# Clock_Updated_3_Nets.net
KiCad netlist of a schematic drawn in EAGLE
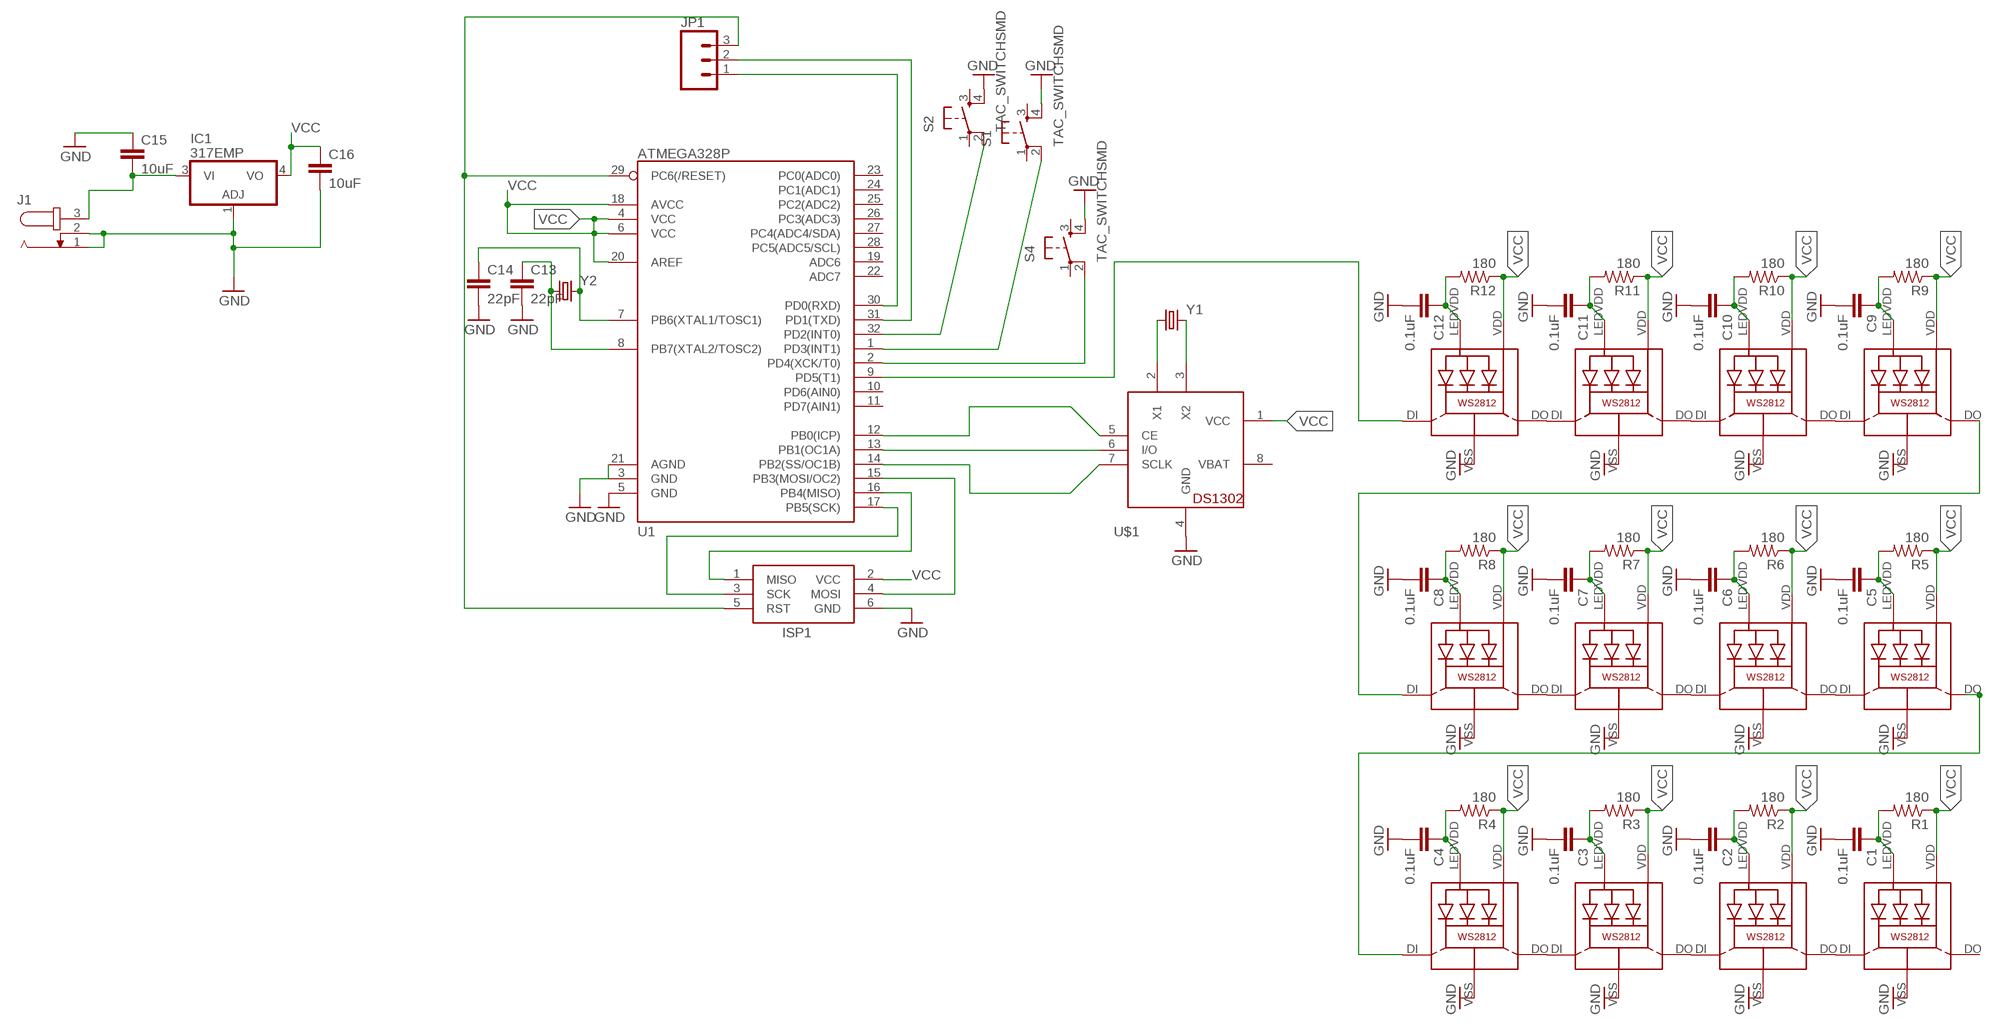
[diagram p0: schematic, sheet 1]

(export (version "E")
  (design (tool "Eeschema 10.0.6"))
  (components
    (comp (ref "C1")
      (value "0.1uF")
      (footprint "eagle-import:0603-CAP")
      (libsource (lib "eagle-import") (part "0.1UF-25V(+80/-20%)(0603)"))
    )
    (comp (ref "C2")
      (value "0.1uF")
      (footprint "eagle-import:0603-CAP")
      (libsource (lib "eagle-import") (part "0.1UF-25V(+80/-20%)(0603)"))
    )
    (comp (ref "C3")
      (value "0.1uF")
      (footprint "eagle-import:0603-CAP")
      (libsource (lib "eagle-import") (part "0.1UF-25V(+80/-20%)(0603)"))
    )
    (comp (ref "C4")
      (value "0.1uF")
      (footprint "eagle-import:0603-CAP")
      (libsource (lib "eagle-import") (part "0.1UF-25V(+80/-20%)(0603)"))
    )
    (comp (ref "C5")
      (value "0.1uF")
      (footprint "eagle-import:0603-CAP")
      (libsource (lib "eagle-import") (part "0.1UF-25V(+80/-20%)(0603)"))
    )
    (comp (ref "C6")
      (value "0.1uF")
      (footprint "eagle-import:0603-CAP")
      (libsource (lib "eagle-import") (part "0.1UF-25V(+80/-20%)(0603)"))
    )
    (comp (ref "C7")
      (value "0.1uF")
      (footprint "eagle-import:0603-CAP")
      (libsource (lib "eagle-import") (part "0.1UF-25V(+80/-20%)(0603)"))
    )
    (comp (ref "C8")
      (value "0.1uF")
      (footprint "eagle-import:0603-CAP")
      (libsource (lib "eagle-import") (part "0.1UF-25V(+80/-20%)(0603)"))
    )
    (comp (ref "C9")
      (value "0.1uF")
      (footprint "eagle-import:0603-CAP")
      (libsource (lib "eagle-import") (part "0.1UF-25V(+80/-20%)(0603)"))
    )
    (comp (ref "C10")
      (value "0.1uF")
      (footprint "eagle-import:0603-CAP")
      (libsource (lib "eagle-import") (part "0.1UF-25V(+80/-20%)(0603)"))
    )
    (comp (ref "C11")
      (value "0.1uF")
      (footprint "eagle-import:0603-CAP")
      (libsource (lib "eagle-import") (part "0.1UF-25V(+80/-20%)(0603)"))
    )
    (comp (ref "C12")
      (value "0.1uF")
      (footprint "eagle-import:0603-CAP")
      (libsource (lib "eagle-import") (part "0.1UF-25V(+80/-20%)(0603)"))
    )
    (comp (ref "C13")
      (value "22pF")
      (footprint "eagle-import:0603-CAP")
      (libsource (lib "eagle-import") (part "22PF-50V-5%(0603)"))
    )
    (comp (ref "C14")
      (value "22pF")
      (footprint "eagle-import:0603-CAP")
      (libsource (lib "eagle-import") (part "22PF-50V-5%(0603)"))
    )
    (comp (ref "C15")
      (value "10uF")
      (footprint "eagle-import:1206")
      (libsource (lib "eagle-import") (part "10UF-6.3V-20%(1206)"))
    )
    (comp (ref "C16")
      (value "10uF")
      (footprint "eagle-import:1206")
      (libsource (lib "eagle-import") (part "10UF-6.3V-20%(1206)"))
    )
    (comp (ref "IC1")
      (value "317EMP")
      (footprint "eagle-import:SOT223")
      (libsource (lib "eagle-import") (part "317EMP"))
    )
    (comp (ref "ISP1")
      (value "AVRISP-6")
      (footprint "eagle-import:AVRISP")
      (libsource (lib "eagle-import") (part "AVRISP-6"))
    )
    (comp (ref "J1")
      (value "JACK-PLUG0")
      (footprint "eagle-import:SPC4077")
      (libsource (lib "eagle-import") (part "JACK-PLUG0"))
    )
    (comp (ref "JP1")
      (value "M03PTH")
      (footprint "eagle-import:1X03")
      (libsource (lib "eagle-import") (part "M03PTH"))
    )
    (comp (ref "LED1")
      (value "WS2812")
      (footprint "eagle-import:WS2812")
      (libsource (lib "eagle-import") (part "WS2812"))
    )
    (comp (ref "LED2")
      (value "WS2812")
      (footprint "eagle-import:WS2812")
      (libsource (lib "eagle-import") (part "WS2812"))
    )
    (comp (ref "LED3")
      (value "WS2812")
      (footprint "eagle-import:WS2812")
      (libsource (lib "eagle-import") (part "WS2812"))
    )
    (comp (ref "LED4")
      (value "WS2812")
      (footprint "eagle-import:WS2812")
      (libsource (lib "eagle-import") (part "WS2812"))
    )
    (comp (ref "LED5")
      (value "WS2812")
      (footprint "eagle-import:WS2812")
      (libsource (lib "eagle-import") (part "WS2812"))
    )
    (comp (ref "LED6")
      (value "WS2812")
      (footprint "eagle-import:WS2812")
      (libsource (lib "eagle-import") (part "WS2812"))
    )
    (comp (ref "LED7")
      (value "WS2812")
      (footprint "eagle-import:WS2812")
      (libsource (lib "eagle-import") (part "WS2812"))
    )
    (comp (ref "LED8")
      (value "WS2812")
      (footprint "eagle-import:WS2812")
      (libsource (lib "eagle-import") (part "WS2812"))
    )
    (comp (ref "LED9")
      (value "WS2812")
      (footprint "eagle-import:WS2812")
      (libsource (lib "eagle-import") (part "WS2812"))
    )
    (comp (ref "LED10")
      (value "WS2812")
      (footprint "eagle-import:WS2812")
      (libsource (lib "eagle-import") (part "WS2812"))
    )
    (comp (ref "LED11")
      (value "WS2812")
      (footprint "eagle-import:WS2812")
      (libsource (lib "eagle-import") (part "WS2812"))
    )
    (comp (ref "LED12")
      (value "WS2812")
      (footprint "eagle-import:WS2812")
      (libsource (lib "eagle-import") (part "WS2812"))
    )
    (comp (ref "R1")
      (value "180")
      (footprint "eagle-import:0603-RES")
      (libsource (lib "eagle-import") (part "180OHM1/10W1%(0603)"))
    )
    (comp (ref "R2")
      (value "180")
      (footprint "eagle-import:0603-RES")
      (libsource (lib "eagle-import") (part "180OHM1/10W1%(0603)"))
    )
    (comp (ref "R3")
      (value "180")
      (footprint "eagle-import:0603-RES")
      (libsource (lib "eagle-import") (part "180OHM1/10W1%(0603)"))
    )
    (comp (ref "R4")
      (value "180")
      (footprint "eagle-import:0603-RES")
      (libsource (lib "eagle-import") (part "180OHM1/10W1%(0603)"))
    )
    (comp (ref "R5")
      (value "180")
      (footprint "eagle-import:0603-RES")
      (libsource (lib "eagle-import") (part "180OHM1/10W1%(0603)"))
    )
    (comp (ref "R6")
      (value "180")
      (footprint "eagle-import:0603-RES")
      (libsource (lib "eagle-import") (part "180OHM1/10W1%(0603)"))
    )
    (comp (ref "R7")
      (value "180")
      (footprint "eagle-import:0603-RES")
      (libsource (lib "eagle-import") (part "180OHM1/10W1%(0603)"))
    )
    (comp (ref "R8")
      (value "180")
      (footprint "eagle-import:0603-RES")
      (libsource (lib "eagle-import") (part "180OHM1/10W1%(0603)"))
    )
    (comp (ref "R9")
      (value "180")
      (footprint "eagle-import:0603-RES")
      (libsource (lib "eagle-import") (part "180OHM1/10W1%(0603)"))
    )
    (comp (ref "R10")
      (value "180")
      (footprint "eagle-import:0603-RES")
      (libsource (lib "eagle-import") (part "180OHM1/10W1%(0603)"))
    )
    (comp (ref "R11")
      (value "180")
      (footprint "eagle-import:0603-RES")
      (libsource (lib "eagle-import") (part "180OHM1/10W1%(0603)"))
    )
    (comp (ref "R12")
      (value "180")
      (footprint "eagle-import:0603-RES")
      (libsource (lib "eagle-import") (part "180OHM1/10W1%(0603)"))
    )
    (comp (ref "S1")
      (value "TAC_SWITCHSMD")
      (footprint "eagle-import:TACTILE-SWITCH-SMD")
      (libsource (lib "eagle-import") (part "TAC_SWITCHSMD"))
    )
    (comp (ref "S2")
      (value "TAC_SWITCHSMD")
      (footprint "eagle-import:TACTILE-SWITCH-SMD")
      (libsource (lib "eagle-import") (part "TAC_SWITCHSMD"))
    )
    (comp (ref "S4")
      (value "TAC_SWITCHSMD")
      (footprint "eagle-import:TACTILE-SWITCH-SMD")
      (libsource (lib "eagle-import") (part "TAC_SWITCHSMD"))
    )
    (comp (ref "U$1")
      (value "DS1302")
      (footprint "eagle-import:DIL08-ROUND")
      (libsource (lib "eagle-import") (part "DS1302"))
    )
    (comp (ref "U1")
      (value "ATMEGA328P")
      (footprint "eagle-import:TQFP32-08")
      (libsource (lib "eagle-import") (part "ATMEGA328_SMT"))
    )
    (comp (ref "Y1")
      (value "CRYSTALTC38H")
      (footprint "eagle-import:TC38H")
      (libsource (lib "eagle-import") (part "CRYSTALTC38H"))
    )
    (comp (ref "Y2")
      (value "CRYSTALSMD")
      (footprint "eagle-import:HC49UP")
      (libsource (lib "eagle-import") (part "CRYSTALSMD"))
    )
  )
  (nets
    (net (code "1") (name "/VBAT") (class "Default")
      (node (ref "U$1") (pin "8") (pinfunction "VBAT_8") (pintype "power_in"))
    )
    (net (code "2") (name "GND") (class "Default")
      (node (ref "C1") (pin "2") (pinfunction "2_2") (pintype "passive"))
      (node (ref "C10") (pin "2") (pinfunction "2_2") (pintype "passive"))
      (node (ref "C11") (pin "2") (pinfunction "2_2") (pintype "passive"))
      (node (ref "C12") (pin "2") (pinfunction "2_2") (pintype "passive"))
      (node (ref "C13") (pin "2") (pinfunction "2_2") (pintype "passive"))
      (node (ref "C14") (pin "2") (pinfunction "2_2") (pintype "passive"))
      (node (ref "C15") (pin "1") (pinfunction "1_1") (pintype "passive"))
      (node (ref "C16") (pin "2") (pinfunction "2_2") (pintype "passive"))
      (node (ref "C2") (pin "2") (pinfunction "2_2") (pintype "passive"))
      (node (ref "C3") (pin "2") (pinfunction "2_2") (pintype "passive"))
      (node (ref "C4") (pin "2") (pinfunction "2_2") (pintype "passive"))
      (node (ref "C5") (pin "2") (pinfunction "2_2") (pintype "passive"))
      (node (ref "C6") (pin "2") (pinfunction "2_2") (pintype "passive"))
      (node (ref "C7") (pin "2") (pinfunction "2_2") (pintype "passive"))
      (node (ref "C8") (pin "2") (pinfunction "2_2") (pintype "passive"))
      (node (ref "C9") (pin "2") (pinfunction "2_2") (pintype "passive"))
      (node (ref "IC1") (pin "1") (pinfunction "ADJ_1") (pintype "input"))
      (node (ref "ISP1") (pin "6") (pinfunction "GND_6") (pintype "power_in"))
      (node (ref "J1") (pin "1") (pinfunction "1_1") (pintype "passive"))
      (node (ref "J1") (pin "2") (pinfunction "2_2") (pintype "passive"))
      (node (ref "LED1") (pin "VSS") (pinfunction "GND_VSS") (pintype "power_in"))
      (node (ref "LED10") (pin "VSS") (pinfunction "GND_VSS") (pintype "power_in"))
      (node (ref "LED11") (pin "VSS") (pinfunction "GND_VSS") (pintype "power_in"))
      (node (ref "LED12") (pin "VSS") (pinfunction "GND_VSS") (pintype "power_in"))
      (node (ref "LED2") (pin "VSS") (pinfunction "GND_VSS") (pintype "power_in"))
      (node (ref "LED3") (pin "VSS") (pinfunction "GND_VSS") (pintype "power_in"))
      (node (ref "LED4") (pin "VSS") (pinfunction "GND_VSS") (pintype "power_in"))
      (node (ref "LED5") (pin "VSS") (pinfunction "GND_VSS") (pintype "power_in"))
      (node (ref "LED6") (pin "VSS") (pinfunction "GND_VSS") (pintype "power_in"))
      (node (ref "LED7") (pin "VSS") (pinfunction "GND_VSS") (pintype "power_in"))
      (node (ref "LED8") (pin "VSS") (pinfunction "GND_VSS") (pintype "power_in"))
      (node (ref "LED9") (pin "VSS") (pinfunction "GND_VSS") (pintype "power_in"))
      (node (ref "S1") (pin "4") (pinfunction "4_4") (pintype "passive"))
      (node (ref "S2") (pin "4") (pinfunction "4_4") (pintype "passive"))
      (node (ref "S4") (pin "4") (pinfunction "4_4") (pintype "passive"))
      (node (ref "U$1") (pin "4") (pinfunction "GND_4") (pintype "power_in"))
      (node (ref "U1") (pin "21") (pinfunction "AGND_21") (pintype "bidirectional"))
      (node (ref "U1") (pin "3") (pinfunction "GND_3") (pintype "bidirectional"))
      (node (ref "U1") (pin "5") (pinfunction "GND_5") (pintype "bidirectional"))
    )
    (net (code "3") (name "Net-(C1-Pad1)") (class "Default")
      (node (ref "C1") (pin "1") (pinfunction "1_1") (pintype "passive"))
      (node (ref "LED1") (pin "LEDVDD") (pinfunction "LEDVDD_LEDVDD") (pintype "power_in"))
      (node (ref "R1") (pin "2") (pinfunction "2_2") (pintype "passive"))
    )
    (net (code "4") (name "Net-(C2-Pad1)") (class "Default")
      (node (ref "C2") (pin "1") (pinfunction "1_1") (pintype "passive"))
      (node (ref "LED2") (pin "LEDVDD") (pinfunction "LEDVDD_LEDVDD") (pintype "power_in"))
      (node (ref "R2") (pin "2") (pinfunction "2_2") (pintype "passive"))
    )
    (net (code "5") (name "Net-(C3-Pad1)") (class "Default")
      (node (ref "C3") (pin "1") (pinfunction "1_1") (pintype "passive"))
      (node (ref "LED3") (pin "LEDVDD") (pinfunction "LEDVDD_LEDVDD") (pintype "power_in"))
      (node (ref "R3") (pin "2") (pinfunction "2_2") (pintype "passive"))
    )
    (net (code "6") (name "Net-(C4-Pad1)") (class "Default")
      (node (ref "C4") (pin "1") (pinfunction "1_1") (pintype "passive"))
      (node (ref "LED4") (pin "LEDVDD") (pinfunction "LEDVDD_LEDVDD") (pintype "power_in"))
      (node (ref "R4") (pin "2") (pinfunction "2_2") (pintype "passive"))
    )
    (net (code "7") (name "Net-(C5-Pad1)") (class "Default")
      (node (ref "C5") (pin "1") (pinfunction "1_1") (pintype "passive"))
      (node (ref "LED5") (pin "LEDVDD") (pinfunction "LEDVDD_LEDVDD") (pintype "power_in"))
      (node (ref "R5") (pin "2") (pinfunction "2_2") (pintype "passive"))
    )
    (net (code "8") (name "Net-(C6-Pad1)") (class "Default")
      (node (ref "C6") (pin "1") (pinfunction "1_1") (pintype "passive"))
      (node (ref "LED6") (pin "LEDVDD") (pinfunction "LEDVDD_LEDVDD") (pintype "power_in"))
      (node (ref "R6") (pin "2") (pinfunction "2_2") (pintype "passive"))
    )
    (net (code "9") (name "Net-(C7-Pad1)") (class "Default")
      (node (ref "C7") (pin "1") (pinfunction "1_1") (pintype "passive"))
      (node (ref "LED7") (pin "LEDVDD") (pinfunction "LEDVDD_LEDVDD") (pintype "power_in"))
      (node (ref "R7") (pin "2") (pinfunction "2_2") (pintype "passive"))
    )
    (net (code "10") (name "Net-(C8-Pad1)") (class "Default")
      (node (ref "C8") (pin "1") (pinfunction "1_1") (pintype "passive"))
      (node (ref "LED8") (pin "LEDVDD") (pinfunction "LEDVDD_LEDVDD") (pintype "power_in"))
      (node (ref "R8") (pin "2") (pinfunction "2_2") (pintype "passive"))
    )
    (net (code "11") (name "Net-(C9-Pad1)") (class "Default")
      (node (ref "C9") (pin "1") (pinfunction "1_1") (pintype "passive"))
      (node (ref "LED9") (pin "LEDVDD") (pinfunction "LEDVDD_LEDVDD") (pintype "power_in"))
      (node (ref "R9") (pin "2") (pinfunction "2_2") (pintype "passive"))
    )
    (net (code "12") (name "Net-(C10-Pad1)") (class "Default")
      (node (ref "C10") (pin "1") (pinfunction "1_1") (pintype "passive"))
      (node (ref "LED10") (pin "LEDVDD") (pinfunction "LEDVDD_LEDVDD") (pintype "power_in"))
      (node (ref "R10") (pin "2") (pinfunction "2_2") (pintype "passive"))
    )
    (net (code "13") (name "Net-(C11-Pad1)") (class "Default")
      (node (ref "C11") (pin "1") (pinfunction "1_1") (pintype "passive"))
      (node (ref "LED11") (pin "LEDVDD") (pinfunction "LEDVDD_LEDVDD") (pintype "power_in"))
      (node (ref "R11") (pin "2") (pinfunction "2_2") (pintype "passive"))
    )
    (net (code "14") (name "Net-(C12-Pad1)") (class "Default")
      (node (ref "C12") (pin "1") (pinfunction "1_1") (pintype "passive"))
      (node (ref "LED12") (pin "LEDVDD") (pinfunction "LEDVDD_LEDVDD") (pintype "power_in"))
      (node (ref "R12") (pin "2") (pinfunction "2_2") (pintype "passive"))
    )
    (net (code "15") (name "Net-(IC1-VI)") (class "Default")
      (node (ref "C15") (pin "2") (pinfunction "2_2") (pintype "passive"))
      (node (ref "IC1") (pin "3") (pinfunction "VI_3") (pintype "input"))
      (node (ref "J1") (pin "3") (pinfunction "3_3") (pintype "passive"))
    )
    (net (code "16") (name "Net-(ISP1-MISO)") (class "Default")
      (node (ref "ISP1") (pin "1") (pinfunction "MISO_1") (pintype "input"))
      (node (ref "U1") (pin "16") (pinfunction "PB4(MISO)_16") (pintype "bidirectional"))
    )
    (net (code "17") (name "Net-(ISP1-MOSI)") (class "Default")
      (node (ref "ISP1") (pin "4") (pinfunction "MOSI_4") (pintype "output"))
      (node (ref "U1") (pin "15") (pinfunction "PB3(MOSI/OC2)_15") (pintype "bidirectional"))
    )
    (net (code "18") (name "Net-(ISP1-RST)") (class "Default")
      (node (ref "ISP1") (pin "5") (pinfunction "RST_5") (pintype "output"))
      (node (ref "JP1") (pin "3") (pinfunction "3_3") (pintype "passive"))
      (node (ref "U1") (pin "29") (pinfunction "PC6(/RESET)_29") (pintype "bidirectional"))
    )
    (net (code "19") (name "Net-(ISP1-SCK)") (class "Default")
      (node (ref "ISP1") (pin "3") (pinfunction "SCK_3") (pintype "output"))
      (node (ref "U1") (pin "17") (pinfunction "PB5(SCK)_17") (pintype "bidirectional"))
    )
    (net (code "20") (name "Net-(LED1-PadDI)") (class "Default")
      (node (ref "LED1") (pin "DI") (pinfunction "DI_DI") (pintype "input"))
      (node (ref "LED2") (pin "DO") (pinfunction "DO_DO") (pintype "output"))
    )
    (net (code "21") (name "Net-(LED2-PadDI)") (class "Default")
      (node (ref "LED2") (pin "DI") (pinfunction "DI_DI") (pintype "input"))
      (node (ref "LED3") (pin "DO") (pinfunction "DO_DO") (pintype "output"))
    )
    (net (code "22") (name "Net-(LED3-PadDI)") (class "Default")
      (node (ref "LED3") (pin "DI") (pinfunction "DI_DI") (pintype "input"))
      (node (ref "LED4") (pin "DO") (pinfunction "DO_DO") (pintype "output"))
    )
    (net (code "23") (name "Net-(LED4-PadDI)") (class "Default")
      (node (ref "LED4") (pin "DI") (pinfunction "DI_DI") (pintype "input"))
      (node (ref "LED5") (pin "DO") (pinfunction "DO_DO") (pintype "output"))
    )
    (net (code "24") (name "Net-(LED5-PadDI)") (class "Default")
      (node (ref "LED5") (pin "DI") (pinfunction "DI_DI") (pintype "input"))
      (node (ref "LED6") (pin "DO") (pinfunction "DO_DO") (pintype "output"))
    )
    (net (code "25") (name "Net-(LED6-PadDI)") (class "Default")
      (node (ref "LED6") (pin "DI") (pinfunction "DI_DI") (pintype "input"))
      (node (ref "LED7") (pin "DO") (pinfunction "DO_DO") (pintype "output"))
    )
    (net (code "26") (name "Net-(LED7-PadDI)") (class "Default")
      (node (ref "LED7") (pin "DI") (pinfunction "DI_DI") (pintype "input"))
      (node (ref "LED8") (pin "DO") (pinfunction "DO_DO") (pintype "output"))
    )
    (net (code "27") (name "Net-(LED8-PadDI)") (class "Default")
      (node (ref "LED8") (pin "DI") (pinfunction "DI_DI") (pintype "input"))
      (node (ref "LED9") (pin "DO") (pinfunction "DO_DO") (pintype "output"))
    )
    (net (code "28") (name "Net-(LED10-PadDI)") (class "Default")
      (node (ref "LED10") (pin "DI") (pinfunction "DI_DI") (pintype "input"))
      (node (ref "LED11") (pin "DO") (pinfunction "DO_DO") (pintype "output"))
    )
    (net (code "29") (name "Net-(LED10-PadDO)") (class "Default")
      (node (ref "LED10") (pin "DO") (pinfunction "DO_DO") (pintype "output"))
      (node (ref "LED9") (pin "DI") (pinfunction "DI_DI") (pintype "input"))
    )
    (net (code "30") (name "Net-(LED11-PadDI)") (class "Default")
      (node (ref "LED11") (pin "DI") (pinfunction "DI_DI") (pintype "input"))
      (node (ref "LED12") (pin "DO") (pinfunction "DO_DO") (pintype "output"))
    )
    (net (code "31") (name "Net-(U$1-CE)") (class "Default")
      (node (ref "U$1") (pin "5") (pinfunction "CE_5") (pintype "input"))
      (node (ref "U1") (pin "12") (pinfunction "PB0(ICP)_12") (pintype "bidirectional"))
    )
    (net (code "32") (name "Net-(U$1-I{slash}O)") (class "Default")
      (node (ref "U$1") (pin "6") (pinfunction "I/O_6") (pintype "bidirectional"))
      (node (ref "U1") (pin "13") (pinfunction "PB1(OC1A)_13") (pintype "bidirectional"))
    )
    (net (code "33") (name "Net-(U$1-SCLK)") (class "Default")
      (node (ref "U$1") (pin "7") (pinfunction "SCLK_7") (pintype "input"))
      (node (ref "U1") (pin "14") (pinfunction "PB2(SS/OC1B)_14") (pintype "bidirectional"))
    )
    (net (code "34") (name "Net-(U$1-X1)") (class "Default")
      (node (ref "U$1") (pin "2") (pinfunction "X1_2") (pintype "passive"))
      (node (ref "Y1") (pin "1") (pinfunction "1_1") (pintype "passive"))
    )
    (net (code "35") (name "Net-(U$1-X2)") (class "Default")
      (node (ref "U$1") (pin "3") (pinfunction "X2_3") (pintype "passive"))
      (node (ref "Y1") (pin "2") (pinfunction "2_2") (pintype "passive"))
    )
    (net (code "36") (name "Net-(U1-PB6(XTAL1{slash}TOSC1))") (class "Default")
      (node (ref "C14") (pin "1") (pinfunction "1_1") (pintype "passive"))
      (node (ref "U1") (pin "7") (pinfunction "PB6(XTAL1/TOSC1)_7") (pintype "bidirectional"))
      (node (ref "Y2") (pin "2") (pinfunction "2_2") (pintype "passive"))
    )
    (net (code "37") (name "Net-(U1-PB7(XTAL2{slash}TOSC2))") (class "Default")
      (node (ref "C13") (pin "1") (pinfunction "1_1") (pintype "passive"))
      (node (ref "U1") (pin "8") (pinfunction "PB7(XTAL2/TOSC2)_8") (pintype "bidirectional"))
      (node (ref "Y2") (pin "1") (pinfunction "1_1") (pintype "passive"))
    )
    (net (code "38") (name "Net-(U1-PD0(RXD))") (class "Default")
      (node (ref "JP1") (pin "1") (pinfunction "1_1") (pintype "passive"))
      (node (ref "U1") (pin "30") (pinfunction "PD0(RXD)_30") (pintype "bidirectional"))
    )
    (net (code "39") (name "Net-(U1-PD1(TXD))") (class "Default")
      (node (ref "JP1") (pin "2") (pinfunction "2_2") (pintype "passive"))
      (node (ref "U1") (pin "31") (pinfunction "PD1(TXD)_31") (pintype "bidirectional"))
    )
    (net (code "40") (name "Net-(U1-PD2(INT0))") (class "Default")
      (node (ref "S2") (pin "2") (pinfunction "2_2") (pintype "passive"))
      (node (ref "U1") (pin "32") (pinfunction "PD2(INT0)_32") (pintype "bidirectional"))
    )
    (net (code "41") (name "Net-(U1-PD3(INT1))") (class "Default")
      (node (ref "S1") (pin "2") (pinfunction "2_2") (pintype "passive"))
      (node (ref "U1") (pin "1") (pinfunction "PD3(INT1)_1") (pintype "bidirectional"))
    )
    (net (code "42") (name "Net-(U1-PD4(XCK{slash}T0))") (class "Default")
      (node (ref "S4") (pin "2") (pinfunction "2_2") (pintype "passive"))
      (node (ref "U1") (pin "2") (pinfunction "PD4(XCK/T0)_2") (pintype "bidirectional"))
    )
    (net (code "43") (name "Net-(U1-PD5(T1))") (class "Default")
      (node (ref "LED12") (pin "DI") (pinfunction "DI_DI") (pintype "input"))
      (node (ref "U1") (pin "9") (pinfunction "PD5(T1)_9") (pintype "bidirectional"))
    )
    (net (code "44") (name "VCC") (class "Default")
      (node (ref "C16") (pin "1") (pinfunction "1_1") (pintype "passive"))
      (node (ref "IC1") (pin "4") (pinfunction "VO_4") (pintype "passive"))
      (node (ref "ISP1") (pin "2") (pinfunction "VCC_2") (pintype "power_in"))
      (node (ref "LED1") (pin "VDD") (pinfunction "VDD_VDD") (pintype "power_in"))
      (node (ref "LED10") (pin "VDD") (pinfunction "VDD_VDD") (pintype "power_in"))
      (node (ref "LED11") (pin "VDD") (pinfunction "VDD_VDD") (pintype "power_in"))
      (node (ref "LED12") (pin "VDD") (pinfunction "VDD_VDD") (pintype "power_in"))
      (node (ref "LED2") (pin "VDD") (pinfunction "VDD_VDD") (pintype "power_in"))
      (node (ref "LED3") (pin "VDD") (pinfunction "VDD_VDD") (pintype "power_in"))
      (node (ref "LED4") (pin "VDD") (pinfunction "VDD_VDD") (pintype "power_in"))
      (node (ref "LED5") (pin "VDD") (pinfunction "VDD_VDD") (pintype "power_in"))
      (node (ref "LED6") (pin "VDD") (pinfunction "VDD_VDD") (pintype "power_in"))
      (node (ref "LED7") (pin "VDD") (pinfunction "VDD_VDD") (pintype "power_in"))
      (node (ref "LED8") (pin "VDD") (pinfunction "VDD_VDD") (pintype "power_in"))
      (node (ref "LED9") (pin "VDD") (pinfunction "VDD_VDD") (pintype "power_in"))
      (node (ref "R1") (pin "1") (pinfunction "1_1") (pintype "passive"))
      (node (ref "R10") (pin "1") (pinfunction "1_1") (pintype "passive"))
      (node (ref "R11") (pin "1") (pinfunction "1_1") (pintype "passive"))
      (node (ref "R12") (pin "1") (pinfunction "1_1") (pintype "passive"))
      (node (ref "R2") (pin "1") (pinfunction "1_1") (pintype "passive"))
      (node (ref "R3") (pin "1") (pinfunction "1_1") (pintype "passive"))
      (node (ref "R4") (pin "1") (pinfunction "1_1") (pintype "passive"))
      (node (ref "R5") (pin "1") (pinfunction "1_1") (pintype "passive"))
      (node (ref "R6") (pin "1") (pinfunction "1_1") (pintype "passive"))
      (node (ref "R7") (pin "1") (pinfunction "1_1") (pintype "passive"))
      (node (ref "R8") (pin "1") (pinfunction "1_1") (pintype "passive"))
      (node (ref "R9") (pin "1") (pinfunction "1_1") (pintype "passive"))
      (node (ref "U$1") (pin "1") (pinfunction "VCC_1") (pintype "power_in"))
      (node (ref "U1") (pin "18") (pinfunction "AVCC_18") (pintype "bidirectional"))
      (node (ref "U1") (pin "20") (pinfunction "AREF_20") (pintype "bidirectional"))
      (node (ref "U1") (pin "4") (pinfunction "VCC_4") (pintype "bidirectional"))
      (node (ref "U1") (pin "6") (pinfunction "VCC_6") (pintype "bidirectional"))
    )
    (net (code "45") (name "unconnected-(LED1-PadDO)") (class "Default")
      (node (ref "LED1") (pin "DO") (pinfunction "DO_DO") (pintype "output"))
    )
    (net (code "46") (name "unconnected-(S1-Pad1)") (class "Default")
      (node (ref "S1") (pin "1") (pinfunction "1_1") (pintype "passive"))
    )
    (net (code "47") (name "unconnected-(S1-Pad3)") (class "Default")
      (node (ref "S1") (pin "3") (pinfunction "3_3") (pintype "passive"))
    )
    (net (code "48") (name "unconnected-(S2-Pad1)") (class "Default")
      (node (ref "S2") (pin "1") (pinfunction "1_1") (pintype "passive"))
    )
    (net (code "49") (name "unconnected-(S2-Pad3)") (class "Default")
      (node (ref "S2") (pin "3") (pinfunction "3_3") (pintype "passive"))
    )
    (net (code "50") (name "unconnected-(S4-Pad1)") (class "Default")
      (node (ref "S4") (pin "1") (pinfunction "1_1") (pintype "passive"))
    )
    (net (code "51") (name "unconnected-(S4-Pad3)") (class "Default")
      (node (ref "S4") (pin "3") (pinfunction "3_3") (pintype "passive"))
    )
    (net (code "52") (name "unconnected-(U1-ADC6-Pad19)") (class "Default")
      (node (ref "U1") (pin "19") (pinfunction "ADC6_19") (pintype "bidirectional"))
    )
    (net (code "53") (name "unconnected-(U1-ADC7-Pad22)") (class "Default")
      (node (ref "U1") (pin "22") (pinfunction "ADC7_22") (pintype "bidirectional"))
    )
    (net (code "54") (name "unconnected-(U1-PC0(ADC0)-Pad23)") (class "Default")
      (node (ref "U1") (pin "23") (pinfunction "PC0(ADC0)_23") (pintype "bidirectional"))
    )
    (net (code "55") (name "unconnected-(U1-PC1(ADC1)-Pad24)") (class "Default")
      (node (ref "U1") (pin "24") (pinfunction "PC1(ADC1)_24") (pintype "bidirectional"))
    )
    (net (code "56") (name "unconnected-(U1-PC2(ADC2)-Pad25)") (class "Default")
      (node (ref "U1") (pin "25") (pinfunction "PC2(ADC2)_25") (pintype "bidirectional"))
    )
    (net (code "57") (name "unconnected-(U1-PC3(ADC3)-Pad26)") (class "Default")
      (node (ref "U1") (pin "26") (pinfunction "PC3(ADC3)_26") (pintype "bidirectional"))
    )
    (net (code "58") (name "unconnected-(U1-PC4(ADC4{slash}SDA)-Pad27)") (class "Default")
      (node (ref "U1") (pin "27") (pinfunction "PC4(ADC4/SDA)_27") (pintype "bidirectional"))
    )
    (net (code "59") (name "unconnected-(U1-PC5(ADC5{slash}SCL)-Pad28)") (class "Default")
      (node (ref "U1") (pin "28") (pinfunction "PC5(ADC5/SCL)_28") (pintype "bidirectional"))
    )
    (net (code "60") (name "unconnected-(U1-PD6(AIN0)-Pad10)") (class "Default")
      (node (ref "U1") (pin "10") (pinfunction "PD6(AIN0)_10") (pintype "bidirectional"))
    )
    (net (code "61") (name "unconnected-(U1-PD7(AIN1)-Pad11)") (class "Default")
      (node (ref "U1") (pin "11") (pinfunction "PD7(AIN1)_11") (pintype "bidirectional"))
    )
  )
)
